# light.net
KiCad netlist of a schematic drawn in Altium Designer
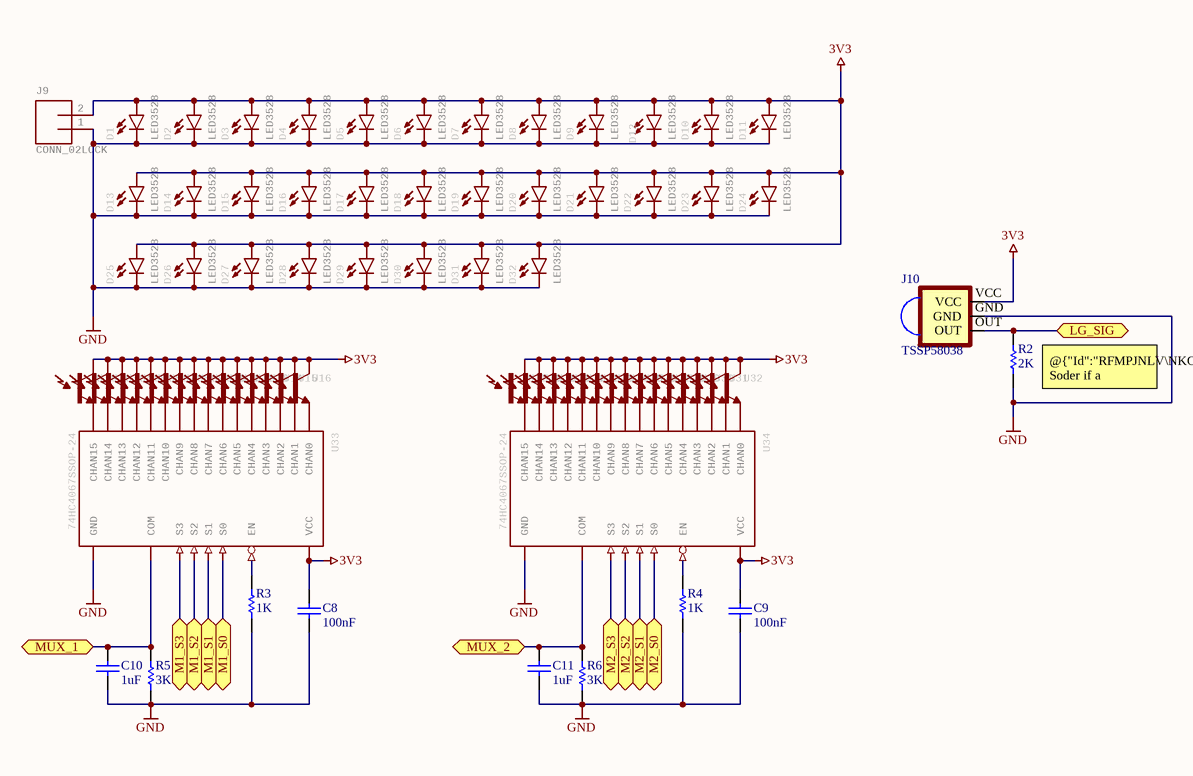
[diagram p0: light.SchDoc]

(export (version "E")
  (design (tool "Eeschema 10.0.6"))
  (components
    (comp (ref "C8")
      (value "100nF")
      (footprint "CAPC1608X90X35ML10T15")
      (description "CAP 100nF")
      (libsource (lib "Hwa Chong Institution") (part "CAPACITOR0603"))
    )
    (comp (ref "C9")
      (value "100nF")
      (footprint "CAPC1608X90X35ML10T15")
      (description "CAP 100nF")
      (libsource (lib "Hwa Chong Institution") (part "CAPACITOR0603"))
    )
    (comp (ref "C10")
      (value "1uF")
      (footprint "CAPC1608X90X35ML10T15")
      (description "CAP 1uF")
      (libsource (lib "Hwa Chong Institution") (part "CAPACITOR0603"))
    )
    (comp (ref "C11")
      (value "1uF")
      (footprint "CAPC1608X90X35ML10T15")
      (description "CAP 1uF")
      (libsource (lib "Hwa Chong Institution") (part "CAPACITOR0603"))
    )
    (comp (ref "D1")
      (value "LED3528")
      (footprint "LED-3528")
      (description "3528-LED")
      (libsource (lib "Hwa Chong Institution") (part "LED3528"))
    )
    (comp (ref "D2")
      (value "LED3528")
      (footprint "LED-3528")
      (description "3528-LED")
      (libsource (lib "Hwa Chong Institution") (part "LED3528"))
    )
    (comp (ref "D3")
      (value "LED3528")
      (footprint "LED-3528")
      (description "3528-LED")
      (libsource (lib "Hwa Chong Institution") (part "LED3528"))
    )
    (comp (ref "D4")
      (value "LED3528")
      (footprint "LED-3528")
      (description "3528-LED")
      (libsource (lib "Hwa Chong Institution") (part "LED3528"))
    )
    (comp (ref "D5")
      (value "LED3528")
      (footprint "LED-3528")
      (description "3528-LED")
      (libsource (lib "Hwa Chong Institution") (part "LED3528"))
    )
    (comp (ref "D6")
      (value "LED3528")
      (footprint "LED-3528")
      (description "3528-LED")
      (libsource (lib "Hwa Chong Institution") (part "LED3528"))
    )
    (comp (ref "D7")
      (value "LED3528")
      (footprint "LED-3528")
      (description "3528-LED")
      (libsource (lib "Hwa Chong Institution") (part "LED3528"))
    )
    (comp (ref "D8")
      (value "LED3528")
      (footprint "LED-3528")
      (description "3528-LED")
      (libsource (lib "Hwa Chong Institution") (part "LED3528"))
    )
    (comp (ref "D9")
      (value "LED3528")
      (footprint "LED-3528")
      (description "3528-LED")
      (libsource (lib "Hwa Chong Institution") (part "LED3528"))
    )
    (comp (ref "D10")
      (value "LED3528")
      (footprint "LED-3528")
      (description "3528-LED")
      (libsource (lib "Hwa Chong Institution") (part "LED3528"))
    )
    (comp (ref "D11")
      (value "LED3528")
      (footprint "LED-3528")
      (description "3528-LED")
      (libsource (lib "Hwa Chong Institution") (part "LED3528"))
    )
    (comp (ref "D12")
      (value "LED3528")
      (footprint "LED-3528")
      (description "3528-LED")
      (libsource (lib "Hwa Chong Institution") (part "LED3528"))
    )
    (comp (ref "D13")
      (value "LED3528")
      (footprint "LED-3528")
      (description "3528-LED")
      (libsource (lib "Hwa Chong Institution") (part "LED3528"))
    )
    (comp (ref "D14")
      (value "LED3528")
      (footprint "LED-3528")
      (description "3528-LED")
      (libsource (lib "Hwa Chong Institution") (part "LED3528"))
    )
    (comp (ref "D15")
      (value "LED3528")
      (footprint "LED-3528")
      (description "3528-LED")
      (libsource (lib "Hwa Chong Institution") (part "LED3528"))
    )
    (comp (ref "D16")
      (value "LED3528")
      (footprint "LED-3528")
      (description "3528-LED")
      (libsource (lib "Hwa Chong Institution") (part "LED3528"))
    )
    (comp (ref "D17")
      (value "LED3528")
      (footprint "LED-3528")
      (description "3528-LED")
      (libsource (lib "Hwa Chong Institution") (part "LED3528"))
    )
    (comp (ref "D18")
      (value "LED3528")
      (footprint "LED-3528")
      (description "3528-LED")
      (libsource (lib "Hwa Chong Institution") (part "LED3528"))
    )
    (comp (ref "D19")
      (value "LED3528")
      (footprint "LED-3528")
      (description "3528-LED")
      (libsource (lib "Hwa Chong Institution") (part "LED3528"))
    )
    (comp (ref "D20")
      (value "LED3528")
      (footprint "LED-3528")
      (description "3528-LED")
      (libsource (lib "Hwa Chong Institution") (part "LED3528"))
    )
    (comp (ref "D21")
      (value "LED3528")
      (footprint "LED-3528")
      (description "3528-LED")
      (libsource (lib "Hwa Chong Institution") (part "LED3528"))
    )
    (comp (ref "D22")
      (value "LED3528")
      (footprint "LED-3528")
      (description "3528-LED")
      (libsource (lib "Hwa Chong Institution") (part "LED3528"))
    )
    (comp (ref "D23")
      (value "LED3528")
      (footprint "LED-3528")
      (description "3528-LED")
      (libsource (lib "Hwa Chong Institution") (part "LED3528"))
    )
    (comp (ref "D24")
      (value "LED3528")
      (footprint "LED-3528")
      (description "3528-LED")
      (libsource (lib "Hwa Chong Institution") (part "LED3528"))
    )
    (comp (ref "D25")
      (value "LED3528")
      (footprint "LED-3528")
      (description "3528-LED")
      (libsource (lib "Hwa Chong Institution") (part "LED3528"))
    )
    (comp (ref "D26")
      (value "LED3528")
      (footprint "LED-3528")
      (description "3528-LED")
      (libsource (lib "Hwa Chong Institution") (part "LED3528"))
    )
    (comp (ref "D27")
      (value "LED3528")
      (footprint "LED-3528")
      (description "3528-LED")
      (libsource (lib "Hwa Chong Institution") (part "LED3528"))
    )
    (comp (ref "D28")
      (value "LED3528")
      (footprint "LED-3528")
      (description "3528-LED")
      (libsource (lib "Hwa Chong Institution") (part "LED3528"))
    )
    (comp (ref "D29")
      (value "LED3528")
      (footprint "LED-3528")
      (description "3528-LED")
      (libsource (lib "Hwa Chong Institution") (part "LED3528"))
    )
    (comp (ref "D30")
      (value "LED3528")
      (footprint "LED-3528")
      (description "3528-LED")
      (libsource (lib "Hwa Chong Institution") (part "LED3528"))
    )
    (comp (ref "D31")
      (value "LED3528")
      (footprint "LED-3528")
      (description "3528-LED")
      (libsource (lib "Hwa Chong Institution") (part "LED3528"))
    )
    (comp (ref "D32")
      (value "LED3528")
      (footprint "LED-3528")
      (description "3528-LED")
      (libsource (lib "Hwa Chong Institution") (part "LED3528"))
    )
    (comp (ref "J9")
      (value "CONN_02LOCK")
      (footprint "1X02_LOCK")
      (libsource (lib "Hwa Chong Institution") (part "CONN_02LOCK"))
    )
    (comp (ref "J10")
      (value "TSSP58038")
      (footprint "TSSP58038")
      (description "38 kHz 25 m 45° 5.5 V Through Hole IR Receiver Module for Light Barrier Systems")
      (fields (field (name "MF") "Vishay"))
      (libsource (lib "Hwa Chong Institution") (part "TSSP58038"))
    )
    (comp (ref "R2")
      (value "2K")
      (footprint "RESISTOR0603")
      (description "RES 2K 0603")
      (libsource (lib "Hwa Chong Institution") (part "RESISTOR0603"))
    )
    (comp (ref "R3")
      (value "1K")
      (footprint "RESISTOR0603")
      (description "RES 1K 0603")
      (libsource (lib "Hwa Chong Institution") (part "RESISTOR0603"))
    )
    (comp (ref "R4")
      (value "1K")
      (footprint "RESISTOR0603")
      (description "RES 1K 0603")
      (libsource (lib "Hwa Chong Institution") (part "RESISTOR0603"))
    )
    (comp (ref "R5")
      (value "3K")
      (footprint "RESISTOR0603")
      (description "RES 3K 0603")
      (libsource (lib "Hwa Chong Institution") (part "RESISTOR0603"))
    )
    (comp (ref "R6")
      (value "3K")
      (footprint "RESISTOR0603")
      (description "RES 3K 0603")
      (libsource (lib "Hwa Chong Institution") (part "RESISTOR0603"))
    )
    (comp (ref "U1")
      (value "LIGHT_SENSOR_ALS")
      (footprint "ALS-PT19")
      (description "Photo Resistor")
      (libsource (lib "Hwa Chong Institution") (part "LIGHT_SENSOR_ALS"))
    )
    (comp (ref "U2")
      (value "LIGHT_SENSOR_ALS")
      (footprint "ALS-PT19")
      (description "Photo Resistor")
      (libsource (lib "Hwa Chong Institution") (part "LIGHT_SENSOR_ALS"))
    )
    (comp (ref "U3")
      (value "LIGHT_SENSOR_ALS")
      (footprint "ALS-PT19")
      (description "Photo Resistor")
      (libsource (lib "Hwa Chong Institution") (part "LIGHT_SENSOR_ALS"))
    )
    (comp (ref "U4")
      (value "LIGHT_SENSOR_ALS")
      (footprint "ALS-PT19")
      (description "Photo Resistor")
      (libsource (lib "Hwa Chong Institution") (part "LIGHT_SENSOR_ALS"))
    )
    (comp (ref "U5")
      (value "LIGHT_SENSOR_ALS")
      (footprint "ALS-PT19")
      (description "Photo Resistor")
      (libsource (lib "Hwa Chong Institution") (part "LIGHT_SENSOR_ALS"))
    )
    (comp (ref "U6")
      (value "LIGHT_SENSOR_ALS")
      (footprint "ALS-PT19")
      (description "Photo Resistor")
      (libsource (lib "Hwa Chong Institution") (part "LIGHT_SENSOR_ALS"))
    )
    (comp (ref "U7")
      (value "LIGHT_SENSOR_ALS")
      (footprint "ALS-PT19")
      (description "Photo Resistor")
      (libsource (lib "Hwa Chong Institution") (part "LIGHT_SENSOR_ALS"))
    )
    (comp (ref "U8")
      (value "LIGHT_SENSOR_ALS")
      (footprint "ALS-PT19")
      (description "Photo Resistor")
      (libsource (lib "Hwa Chong Institution") (part "LIGHT_SENSOR_ALS"))
    )
    (comp (ref "U9")
      (value "LIGHT_SENSOR_ALS")
      (footprint "ALS-PT19")
      (description "Photo Resistor")
      (libsource (lib "Hwa Chong Institution") (part "LIGHT_SENSOR_ALS"))
    )
    (comp (ref "U10")
      (value "LIGHT_SENSOR_ALS")
      (footprint "ALS-PT19")
      (description "Photo Resistor")
      (libsource (lib "Hwa Chong Institution") (part "LIGHT_SENSOR_ALS"))
    )
    (comp (ref "U11")
      (value "LIGHT_SENSOR_ALS")
      (footprint "ALS-PT19")
      (description "Photo Resistor")
      (libsource (lib "Hwa Chong Institution") (part "LIGHT_SENSOR_ALS"))
    )
    (comp (ref "U12")
      (value "LIGHT_SENSOR_ALS")
      (footprint "ALS-PT19")
      (description "Photo Resistor")
      (libsource (lib "Hwa Chong Institution") (part "LIGHT_SENSOR_ALS"))
    )
    (comp (ref "U13")
      (value "LIGHT_SENSOR_ALS")
      (footprint "ALS-PT19")
      (description "Photo Resistor")
      (libsource (lib "Hwa Chong Institution") (part "LIGHT_SENSOR_ALS"))
    )
    (comp (ref "U14")
      (value "LIGHT_SENSOR_ALS")
      (footprint "ALS-PT19")
      (description "Photo Resistor")
      (libsource (lib "Hwa Chong Institution") (part "LIGHT_SENSOR_ALS"))
    )
    (comp (ref "U15")
      (value "LIGHT_SENSOR_ALS")
      (footprint "ALS-PT19")
      (description "Photo Resistor")
      (libsource (lib "Hwa Chong Institution") (part "LIGHT_SENSOR_ALS"))
    )
    (comp (ref "U16")
      (value "LIGHT_SENSOR_ALS")
      (footprint "ALS-PT19")
      (description "Photo Resistor")
      (libsource (lib "Hwa Chong Institution") (part "LIGHT_SENSOR_ALS"))
    )
    (comp (ref "U17")
      (value "LIGHT_SENSOR_ALS")
      (footprint "ALS-PT19")
      (description "Photo Resistor")
      (libsource (lib "Hwa Chong Institution") (part "LIGHT_SENSOR_ALS"))
    )
    (comp (ref "U18")
      (value "LIGHT_SENSOR_ALS")
      (footprint "ALS-PT19")
      (description "Photo Resistor")
      (libsource (lib "Hwa Chong Institution") (part "LIGHT_SENSOR_ALS"))
    )
    (comp (ref "U19")
      (value "LIGHT_SENSOR_ALS")
      (footprint "ALS-PT19")
      (description "Photo Resistor")
      (libsource (lib "Hwa Chong Institution") (part "LIGHT_SENSOR_ALS"))
    )
    (comp (ref "U20")
      (value "LIGHT_SENSOR_ALS")
      (footprint "ALS-PT19")
      (description "Photo Resistor")
      (libsource (lib "Hwa Chong Institution") (part "LIGHT_SENSOR_ALS"))
    )
    (comp (ref "U21")
      (value "LIGHT_SENSOR_ALS")
      (footprint "ALS-PT19")
      (description "Photo Resistor")
      (libsource (lib "Hwa Chong Institution") (part "LIGHT_SENSOR_ALS"))
    )
    (comp (ref "U22")
      (value "LIGHT_SENSOR_ALS")
      (footprint "ALS-PT19")
      (description "Photo Resistor")
      (libsource (lib "Hwa Chong Institution") (part "LIGHT_SENSOR_ALS"))
    )
    (comp (ref "U23")
      (value "LIGHT_SENSOR_ALS")
      (footprint "ALS-PT19")
      (description "Photo Resistor")
      (libsource (lib "Hwa Chong Institution") (part "LIGHT_SENSOR_ALS"))
    )
    (comp (ref "U24")
      (value "LIGHT_SENSOR_ALS")
      (footprint "ALS-PT19")
      (description "Photo Resistor")
      (libsource (lib "Hwa Chong Institution") (part "LIGHT_SENSOR_ALS"))
    )
    (comp (ref "U25")
      (value "LIGHT_SENSOR_ALS")
      (footprint "ALS-PT19")
      (description "Photo Resistor")
      (libsource (lib "Hwa Chong Institution") (part "LIGHT_SENSOR_ALS"))
    )
    (comp (ref "U26")
      (value "LIGHT_SENSOR_ALS")
      (footprint "ALS-PT19")
      (description "Photo Resistor")
      (libsource (lib "Hwa Chong Institution") (part "LIGHT_SENSOR_ALS"))
    )
    (comp (ref "U27")
      (value "LIGHT_SENSOR_ALS")
      (footprint "ALS-PT19")
      (description "Photo Resistor")
      (libsource (lib "Hwa Chong Institution") (part "LIGHT_SENSOR_ALS"))
    )
    (comp (ref "U28")
      (value "LIGHT_SENSOR_ALS")
      (footprint "ALS-PT19")
      (description "Photo Resistor")
      (libsource (lib "Hwa Chong Institution") (part "LIGHT_SENSOR_ALS"))
    )
    (comp (ref "U29")
      (value "LIGHT_SENSOR_ALS")
      (footprint "ALS-PT19")
      (description "Photo Resistor")
      (libsource (lib "Hwa Chong Institution") (part "LIGHT_SENSOR_ALS"))
    )
    (comp (ref "U30")
      (value "LIGHT_SENSOR_ALS")
      (footprint "ALS-PT19")
      (description "Photo Resistor")
      (libsource (lib "Hwa Chong Institution") (part "LIGHT_SENSOR_ALS"))
    )
    (comp (ref "U31")
      (value "LIGHT_SENSOR_ALS")
      (footprint "ALS-PT19")
      (description "Photo Resistor")
      (libsource (lib "Hwa Chong Institution") (part "LIGHT_SENSOR_ALS"))
    )
    (comp (ref "U32")
      (value "LIGHT_SENSOR_ALS")
      (footprint "ALS-PT19")
      (description "Photo Resistor")
      (libsource (lib "Hwa Chong Institution") (part "LIGHT_SENSOR_ALS"))
    )
    (comp (ref "U33")
      (value "74HC4067SSOP-24")
      (footprint "SSOP24")
      (description "16 Channel Analog MUX")
      (libsource (lib "Hwa Chong Institution") (part "74HC4067SSOP-24"))
    )
    (comp (ref "U34")
      (value "74HC4067SSOP-24")
      (footprint "SSOP24")
      (description "16 Channel Analog MUX")
      (libsource (lib "Hwa Chong Institution") (part "74HC4067SSOP-24"))
    )
  )
  (nets
    (net (code "1") (name "/LG_SIG") (class "Default")
      (node (ref "J10") (pin "OUT") (pinfunction "OUT_OUT") (pintype "bidirectional"))
      (node (ref "R2") (pin "2") (pinfunction "2_2") (pintype "passive"))
    )
    (net (code "2") (name "/M1_S0") (class "Default")
      (node (ref "U33") (pin "10") (pinfunction "S0_10") (pintype "input"))
    )
    (net (code "3") (name "/M1_S1") (class "Default")
      (node (ref "U33") (pin "11") (pinfunction "S1_11") (pintype "input"))
    )
    (net (code "4") (name "/M1_S2") (class "Default")
      (node (ref "U33") (pin "14") (pinfunction "S2_14") (pintype "input"))
    )
    (net (code "5") (name "/M1_S3") (class "Default")
      (node (ref "U33") (pin "13") (pinfunction "S3_13") (pintype "input"))
    )
    (net (code "6") (name "/M2_S0") (class "Default")
      (node (ref "U34") (pin "10") (pinfunction "S0_10") (pintype "input"))
    )
    (net (code "7") (name "/M2_S1") (class "Default")
      (node (ref "U34") (pin "11") (pinfunction "S1_11") (pintype "input"))
    )
    (net (code "8") (name "/M2_S2") (class "Default")
      (node (ref "U34") (pin "14") (pinfunction "S2_14") (pintype "input"))
    )
    (net (code "9") (name "/M2_S3") (class "Default")
      (node (ref "U34") (pin "13") (pinfunction "S3_13") (pintype "input"))
    )
    (net (code "10") (name "/MUX_1") (class "Default")
      (node (ref "C10") (pin "2") (pinfunction "2_2") (pintype "passive"))
      (node (ref "R5") (pin "2") (pinfunction "2_2") (pintype "passive"))
      (node (ref "U33") (pin "1") (pinfunction "COM_1") (pintype "bidirectional"))
    )
    (net (code "11") (name "/MUX_2") (class "Default")
      (node (ref "C11") (pin "2") (pinfunction "2_2") (pintype "passive"))
      (node (ref "R6") (pin "2") (pinfunction "2_2") (pintype "passive"))
      (node (ref "U34") (pin "1") (pinfunction "COM_1") (pintype "bidirectional"))
    )
    (net (code "12") (name "3V3") (class "Default")
      (node (ref "C8") (pin "2") (pinfunction "2_2") (pintype "passive"))
      (node (ref "C9") (pin "2") (pinfunction "2_2") (pintype "passive"))
      (node (ref "D1") (pin "1") (pinfunction "A_1") (pintype "passive"))
      (node (ref "D10") (pin "1") (pinfunction "A_1") (pintype "passive"))
      (node (ref "D11") (pin "1") (pinfunction "A_1") (pintype "passive"))
      (node (ref "D12") (pin "1") (pinfunction "A_1") (pintype "passive"))
      (node (ref "D13") (pin "1") (pinfunction "A_1") (pintype "passive"))
      (node (ref "D14") (pin "1") (pinfunction "A_1") (pintype "passive"))
      (node (ref "D15") (pin "1") (pinfunction "A_1") (pintype "passive"))
      (node (ref "D16") (pin "1") (pinfunction "A_1") (pintype "passive"))
      (node (ref "D17") (pin "1") (pinfunction "A_1") (pintype "passive"))
      (node (ref "D18") (pin "1") (pinfunction "A_1") (pintype "passive"))
      (node (ref "D19") (pin "1") (pinfunction "A_1") (pintype "passive"))
      (node (ref "D2") (pin "1") (pinfunction "A_1") (pintype "passive"))
      (node (ref "D20") (pin "1") (pinfunction "A_1") (pintype "passive"))
      (node (ref "D21") (pin "1") (pinfunction "A_1") (pintype "passive"))
      (node (ref "D22") (pin "1") (pinfunction "A_1") (pintype "passive"))
      (node (ref "D23") (pin "1") (pinfunction "A_1") (pintype "passive"))
      (node (ref "D24") (pin "1") (pinfunction "A_1") (pintype "passive"))
      (node (ref "D25") (pin "1") (pinfunction "A_1") (pintype "passive"))
      (node (ref "D26") (pin "1") (pinfunction "A_1") (pintype "passive"))
      (node (ref "D27") (pin "1") (pinfunction "A_1") (pintype "passive"))
      (node (ref "D28") (pin "1") (pinfunction "A_1") (pintype "passive"))
      (node (ref "D29") (pin "1") (pinfunction "A_1") (pintype "passive"))
      (node (ref "D3") (pin "1") (pinfunction "A_1") (pintype "passive"))
      (node (ref "D30") (pin "1") (pinfunction "A_1") (pintype "passive"))
      (node (ref "D31") (pin "1") (pinfunction "A_1") (pintype "passive"))
      (node (ref "D32") (pin "1") (pinfunction "A_1") (pintype "passive"))
      (node (ref "D4") (pin "1") (pinfunction "A_1") (pintype "passive"))
      (node (ref "D5") (pin "1") (pinfunction "A_1") (pintype "passive"))
      (node (ref "D6") (pin "1") (pinfunction "A_1") (pintype "passive"))
      (node (ref "D7") (pin "1") (pinfunction "A_1") (pintype "passive"))
      (node (ref "D8") (pin "1") (pinfunction "A_1") (pintype "passive"))
      (node (ref "D9") (pin "1") (pinfunction "A_1") (pintype "passive"))
      (node (ref "J10") (pin "VCC") (pinfunction "VCC_VCC") (pintype "power_in"))
      (node (ref "J9") (pin "2") (pinfunction "2_2") (pintype "passive"))
      (node (ref "U1") (pin "1") (pinfunction "C1_1") (pintype "passive"))
      (node (ref "U10") (pin "1") (pinfunction "C1_1") (pintype "passive"))
      (node (ref "U11") (pin "1") (pinfunction "C1_1") (pintype "passive"))
      (node (ref "U12") (pin "1") (pinfunction "C1_1") (pintype "passive"))
      (node (ref "U13") (pin "1") (pinfunction "C1_1") (pintype "passive"))
      (node (ref "U14") (pin "1") (pinfunction "C1_1") (pintype "passive"))
      (node (ref "U15") (pin "1") (pinfunction "C1_1") (pintype "passive"))
      (node (ref "U16") (pin "1") (pinfunction "C1_1") (pintype "passive"))
      (node (ref "U17") (pin "1") (pinfunction "C1_1") (pintype "passive"))
      (node (ref "U18") (pin "1") (pinfunction "C1_1") (pintype "passive"))
      (node (ref "U19") (pin "1") (pinfunction "C1_1") (pintype "passive"))
      (node (ref "U2") (pin "1") (pinfunction "C1_1") (pintype "passive"))
      (node (ref "U20") (pin "1") (pinfunction "C1_1") (pintype "passive"))
      (node (ref "U21") (pin "1") (pinfunction "C1_1") (pintype "passive"))
      (node (ref "U22") (pin "1") (pinfunction "C1_1") (pintype "passive"))
      (node (ref "U23") (pin "1") (pinfunction "C1_1") (pintype "passive"))
      (node (ref "U24") (pin "1") (pinfunction "C1_1") (pintype "passive"))
      (node (ref "U25") (pin "1") (pinfunction "C1_1") (pintype "passive"))
      (node (ref "U26") (pin "1") (pinfunction "C1_1") (pintype "passive"))
      (node (ref "U27") (pin "1") (pinfunction "C1_1") (pintype "passive"))
      (node (ref "U28") (pin "1") (pinfunction "C1_1") (pintype "passive"))
      (node (ref "U29") (pin "1") (pinfunction "C1_1") (pintype "passive"))
      (node (ref "U3") (pin "1") (pinfunction "C1_1") (pintype "passive"))
      (node (ref "U30") (pin "1") (pinfunction "C1_1") (pintype "passive"))
      (node (ref "U31") (pin "1") (pinfunction "C1_1") (pintype "passive"))
      (node (ref "U32") (pin "1") (pinfunction "C1_1") (pintype "passive"))
      (node (ref "U33") (pin "24") (pinfunction "VCC_24") (pintype "power_in"))
      (node (ref "U34") (pin "24") (pinfunction "VCC_24") (pintype "power_in"))
      (node (ref "U4") (pin "1") (pinfunction "C1_1") (pintype "passive"))
      (node (ref "U5") (pin "1") (pinfunction "C1_1") (pintype "passive"))
      (node (ref "U6") (pin "1") (pinfunction "C1_1") (pintype "passive"))
      (node (ref "U7") (pin "1") (pinfunction "C1_1") (pintype "passive"))
      (node (ref "U8") (pin "1") (pinfunction "C1_1") (pintype "passive"))
      (node (ref "U9") (pin "1") (pinfunction "C1_1") (pintype "passive"))
    )
    (net (code "13") (name "GND") (class "Default")
      (node (ref "C10") (pin "1") (pinfunction "1_1") (pintype "passive"))
      (node (ref "C11") (pin "1") (pinfunction "1_1") (pintype "passive"))
      (node (ref "C8") (pin "1") (pinfunction "1_1") (pintype "passive"))
      (node (ref "C9") (pin "1") (pinfunction "1_1") (pintype "passive"))
      (node (ref "D1") (pin "2") (pinfunction "C_2") (pintype "passive"))
      (node (ref "D10") (pin "2") (pinfunction "C_2") (pintype "passive"))
      (node (ref "D11") (pin "2") (pinfunction "C_2") (pintype "passive"))
      (node (ref "D12") (pin "2") (pinfunction "C_2") (pintype "passive"))
      (node (ref "D13") (pin "2") (pinfunction "C_2") (pintype "passive"))
      (node (ref "D14") (pin "2") (pinfunction "C_2") (pintype "passive"))
      (node (ref "D15") (pin "2") (pinfunction "C_2") (pintype "passive"))
      (node (ref "D16") (pin "2") (pinfunction "C_2") (pintype "passive"))
      (node (ref "D17") (pin "2") (pinfunction "C_2") (pintype "passive"))
      (node (ref "D18") (pin "2") (pinfunction "C_2") (pintype "passive"))
      (node (ref "D19") (pin "2") (pinfunction "C_2") (pintype "passive"))
      (node (ref "D2") (pin "2") (pinfunction "C_2") (pintype "passive"))
      (node (ref "D20") (pin "2") (pinfunction "C_2") (pintype "passive"))
      (node (ref "D21") (pin "2") (pinfunction "C_2") (pintype "passive"))
      (node (ref "D22") (pin "2") (pinfunction "C_2") (pintype "passive"))
      (node (ref "D23") (pin "2") (pinfunction "C_2") (pintype "passive"))
      (node (ref "D24") (pin "2") (pinfunction "C_2") (pintype "passive"))
      (node (ref "D25") (pin "2") (pinfunction "C_2") (pintype "passive"))
      (node (ref "D26") (pin "2") (pinfunction "C_2") (pintype "passive"))
      (node (ref "D27") (pin "2") (pinfunction "C_2") (pintype "passive"))
      (node (ref "D28") (pin "2") (pinfunction "C_2") (pintype "passive"))
      (node (ref "D29") (pin "2") (pinfunction "C_2") (pintype "passive"))
      (node (ref "D3") (pin "2") (pinfunction "C_2") (pintype "passive"))
      (node (ref "D30") (pin "2") (pinfunction "C_2") (pintype "passive"))
      (node (ref "D31") (pin "2") (pinfunction "C_2") (pintype "passive"))
      (node (ref "D32") (pin "2") (pinfunction "C_2") (pintype "passive"))
      (node (ref "D4") (pin "2") (pinfunction "C_2") (pintype "passive"))
      (node (ref "D5") (pin "2") (pinfunction "C_2") (pintype "passive"))
      (node (ref "D6") (pin "2") (pinfunction "C_2") (pintype "passive"))
      (node (ref "D7") (pin "2") (pinfunction "C_2") (pintype "passive"))
      (node (ref "D8") (pin "2") (pinfunction "C_2") (pintype "passive"))
      (node (ref "D9") (pin "2") (pinfunction "C_2") (pintype "passive"))
      (node (ref "J10") (pin "GND") (pinfunction "GND_GND") (pintype "power_in"))
      (node (ref "J9") (pin "1") (pinfunction "1_1") (pintype "passive"))
      (node (ref "R2") (pin "1") (pinfunction "1_1") (pintype "passive"))
      (node (ref "R3") (pin "1") (pinfunction "1_1") (pintype "passive"))
      (node (ref "R4") (pin "1") (pinfunction "1_1") (pintype "passive"))
      (node (ref "R5") (pin "1") (pinfunction "1_1") (pintype "passive"))
      (node (ref "R6") (pin "1") (pinfunction "1_1") (pintype "passive"))
      (node (ref "U33") (pin "12") (pinfunction "GND_12") (pintype "power_in"))
      (node (ref "U34") (pin "12") (pinfunction "GND_12") (pintype "power_in"))
    )
    (net (code "14") (name "Net-(U1-E1)") (class "Default")
      (node (ref "U1") (pin "2") (pinfunction "E1_2") (pintype "passive"))
      (node (ref "U33") (pin "16") (pinfunction "CHAN15_16") (pintype "bidirectional"))
    )
    (net (code "15") (name "Net-(U2-E1)") (class "Default")
      (node (ref "U2") (pin "2") (pinfunction "E1_2") (pintype "passive"))
      (node (ref "U33") (pin "17") (pinfunction "CHAN14_17") (pintype "bidirectional"))
    )
    (net (code "16") (name "Net-(U3-E1)") (class "Default")
      (node (ref "U3") (pin "2") (pinfunction "E1_2") (pintype "passive"))
      (node (ref "U33") (pin "18") (pinfunction "CHAN13_18") (pintype "bidirectional"))
    )
    (net (code "17") (name "Net-(U10-E1)") (class "Default")
      (node (ref "U10") (pin "2") (pinfunction "E1_2") (pintype "passive"))
      (node (ref "U33") (pin "3") (pinfunction "CHAN6_3") (pintype "bidirectional"))
    )
    (net (code "18") (name "Net-(U11-E1)") (class "Default")
      (node (ref "U11") (pin "2") (pinfunction "E1_2") (pintype "passive"))
      (node (ref "U33") (pin "4") (pinfunction "CHAN5_4") (pintype "bidirectional"))
    )
    (net (code "19") (name "Net-(U12-E1)") (class "Default")
      (node (ref "U12") (pin "2") (pinfunction "E1_2") (pintype "passive"))
      (node (ref "U33") (pin "5") (pinfunction "CHAN4_5") (pintype "bidirectional"))
    )
    (net (code "20") (name "Net-(U13-E1)") (class "Default")
      (node (ref "U13") (pin "2") (pinfunction "E1_2") (pintype "passive"))
      (node (ref "U33") (pin "6") (pinfunction "CHAN3_6") (pintype "bidirectional"))
    )
    (net (code "21") (name "Net-(U14-E1)") (class "Default")
      (node (ref "U14") (pin "2") (pinfunction "E1_2") (pintype "passive"))
      (node (ref "U33") (pin "7") (pinfunction "CHAN2_7") (pintype "bidirectional"))
    )
    (net (code "22") (name "Net-(U15-E1)") (class "Default")
      (node (ref "U15") (pin "2") (pinfunction "E1_2") (pintype "passive"))
      (node (ref "U33") (pin "8") (pinfunction "CHAN1_8") (pintype "bidirectional"))
    )
    (net (code "23") (name "Net-(U16-E1)") (class "Default")
      (node (ref "U16") (pin "2") (pinfunction "E1_2") (pintype "passive"))
      (node (ref "U33") (pin "9") (pinfunction "CHAN0_9") (pintype "bidirectional"))
    )
    (net (code "24") (name "Net-(U17-E1)") (class "Default")
      (node (ref "U17") (pin "2") (pinfunction "E1_2") (pintype "passive"))
      (node (ref "U34") (pin "16") (pinfunction "CHAN15_16") (pintype "bidirectional"))
    )
    (net (code "25") (name "Net-(U18-E1)") (class "Default")
      (node (ref "U18") (pin "2") (pinfunction "E1_2") (pintype "passive"))
      (node (ref "U34") (pin "17") (pinfunction "CHAN14_17") (pintype "bidirectional"))
    )
    (net (code "26") (name "Net-(U19-E1)") (class "Default")
      (node (ref "U19") (pin "2") (pinfunction "E1_2") (pintype "passive"))
      (node (ref "U34") (pin "18") (pinfunction "CHAN13_18") (pintype "bidirectional"))
    )
    (net (code "27") (name "Net-(U20-E1)") (class "Default")
      (node (ref "U20") (pin "2") (pinfunction "E1_2") (pintype "passive"))
      (node (ref "U34") (pin "19") (pinfunction "CHAN12_19") (pintype "bidirectional"))
    )
    (net (code "28") (name "Net-(U21-E1)") (class "Default")
      (node (ref "U21") (pin "2") (pinfunction "E1_2") (pintype "passive"))
      (node (ref "U34") (pin "20") (pinfunction "CHAN11_20") (pintype "bidirectional"))
    )
    (net (code "29") (name "Net-(U22-E1)") (class "Default")
      (node (ref "U22") (pin "2") (pinfunction "E1_2") (pintype "passive"))
      (node (ref "U34") (pin "21") (pinfunction "CHAN10_21") (pintype "bidirectional"))
    )
    (net (code "30") (name "Net-(U23-E1)") (class "Default")
      (node (ref "U23") (pin "2") (pinfunction "E1_2") (pintype "passive"))
      (node (ref "U34") (pin "22") (pinfunction "CHAN9_22") (pintype "bidirectional"))
    )
    (net (code "31") (name "Net-(U24-E1)") (class "Default")
      (node (ref "U24") (pin "2") (pinfunction "E1_2") (pintype "passive"))
      (node (ref "U34") (pin "23") (pinfunction "CHAN8_23") (pintype "bidirectional"))
    )
    (net (code "32") (name "Net-(U25-E1)") (class "Default")
      (node (ref "U25") (pin "2") (pinfunction "E1_2") (pintype "passive"))
      (node (ref "U34") (pin "2") (pinfunction "CHAN7_2") (pintype "bidirectional"))
    )
    (net (code "33") (name "Net-(U26-E1)") (class "Default")
      (node (ref "U26") (pin "2") (pinfunction "E1_2") (pintype "passive"))
      (node (ref "U34") (pin "3") (pinfunction "CHAN6_3") (pintype "bidirectional"))
    )
    (net (code "34") (name "Net-(U27-E1)") (class "Default")
      (node (ref "U27") (pin "2") (pinfunction "E1_2") (pintype "passive"))
      (node (ref "U34") (pin "4") (pinfunction "CHAN5_4") (pintype "bidirectional"))
    )
    (net (code "35") (name "Net-(U28-E1)") (class "Default")
      (node (ref "U28") (pin "2") (pinfunction "E1_2") (pintype "passive"))
      (node (ref "U34") (pin "5") (pinfunction "CHAN4_5") (pintype "bidirectional"))
    )
    (net (code "36") (name "Net-(U29-E1)") (class "Default")
      (node (ref "U29") (pin "2") (pinfunction "E1_2") (pintype "passive"))
      (node (ref "U34") (pin "6") (pinfunction "CHAN3_6") (pintype "bidirectional"))
    )
    (net (code "37") (name "Net-(U30-E1)") (class "Default")
      (node (ref "U30") (pin "2") (pinfunction "E1_2") (pintype "passive"))
      (node (ref "U34") (pin "7") (pinfunction "CHAN2_7") (pintype "bidirectional"))
    )
    (net (code "38") (name "Net-(U31-E1)") (class "Default")
      (node (ref "U31") (pin "2") (pinfunction "E1_2") (pintype "passive"))
      (node (ref "U34") (pin "8") (pinfunction "CHAN1_8") (pintype "bidirectional"))
    )
    (net (code "39") (name "Net-(U32-E1)") (class "Default")
      (node (ref "U32") (pin "2") (pinfunction "E1_2") (pintype "passive"))
      (node (ref "U34") (pin "9") (pinfunction "CHAN0_9") (pintype "bidirectional"))
    )
    (net (code "40") (name "Net-(U33-CHAN7)") (class "Default")
      (node (ref "U33") (pin "2") (pinfunction "CHAN7_2") (pintype "bidirectional"))
      (node (ref "U9") (pin "2") (pinfunction "E1_2") (pintype "passive"))
    )
    (net (code "41") (name "Net-(U33-CHAN8)") (class "Default")
      (node (ref "U33") (pin "23") (pinfunction "CHAN8_23") (pintype "bidirectional"))
      (node (ref "U8") (pin "2") (pinfunction "E1_2") (pintype "passive"))
    )
    (net (code "42") (name "Net-(U33-CHAN9)") (class "Default")
      (node (ref "U33") (pin "22") (pinfunction "CHAN9_22") (pintype "bidirectional"))
      (node (ref "U7") (pin "2") (pinfunction "E1_2") (pintype "passive"))
    )
    (net (code "43") (name "Net-(U33-CHAN10)") (class "Default")
      (node (ref "U33") (pin "21") (pinfunction "CHAN10_21") (pintype "bidirectional"))
      (node (ref "U6") (pin "2") (pinfunction "E1_2") (pintype "passive"))
    )
    (net (code "44") (name "Net-(U33-CHAN11)") (class "Default")
      (node (ref "U33") (pin "20") (pinfunction "CHAN11_20") (pintype "bidirectional"))
      (node (ref "U5") (pin "2") (pinfunction "E1_2") (pintype "passive"))
    )
    (net (code "45") (name "Net-(U33-CHAN12)") (class "Default")
      (node (ref "U33") (pin "19") (pinfunction "CHAN12_19") (pintype "bidirectional"))
      (node (ref "U4") (pin "2") (pinfunction "E1_2") (pintype "passive"))
    )
    (net (code "46") (name "Net-(U33-EN)") (class "Default")
      (node (ref "R3") (pin "2") (pinfunction "2_2") (pintype "passive"))
      (node (ref "U33") (pin "15") (pinfunction "EN_15") (pintype "input"))
    )
    (net (code "47") (name "Net-(U34-EN)") (class "Default")
      (node (ref "R4") (pin "2") (pinfunction "2_2") (pintype "passive"))
      (node (ref "U34") (pin "15") (pinfunction "EN_15") (pintype "input"))
    )
  )
)
